# numeric.net
KiCad netlist of a schematic drawn in EAGLE
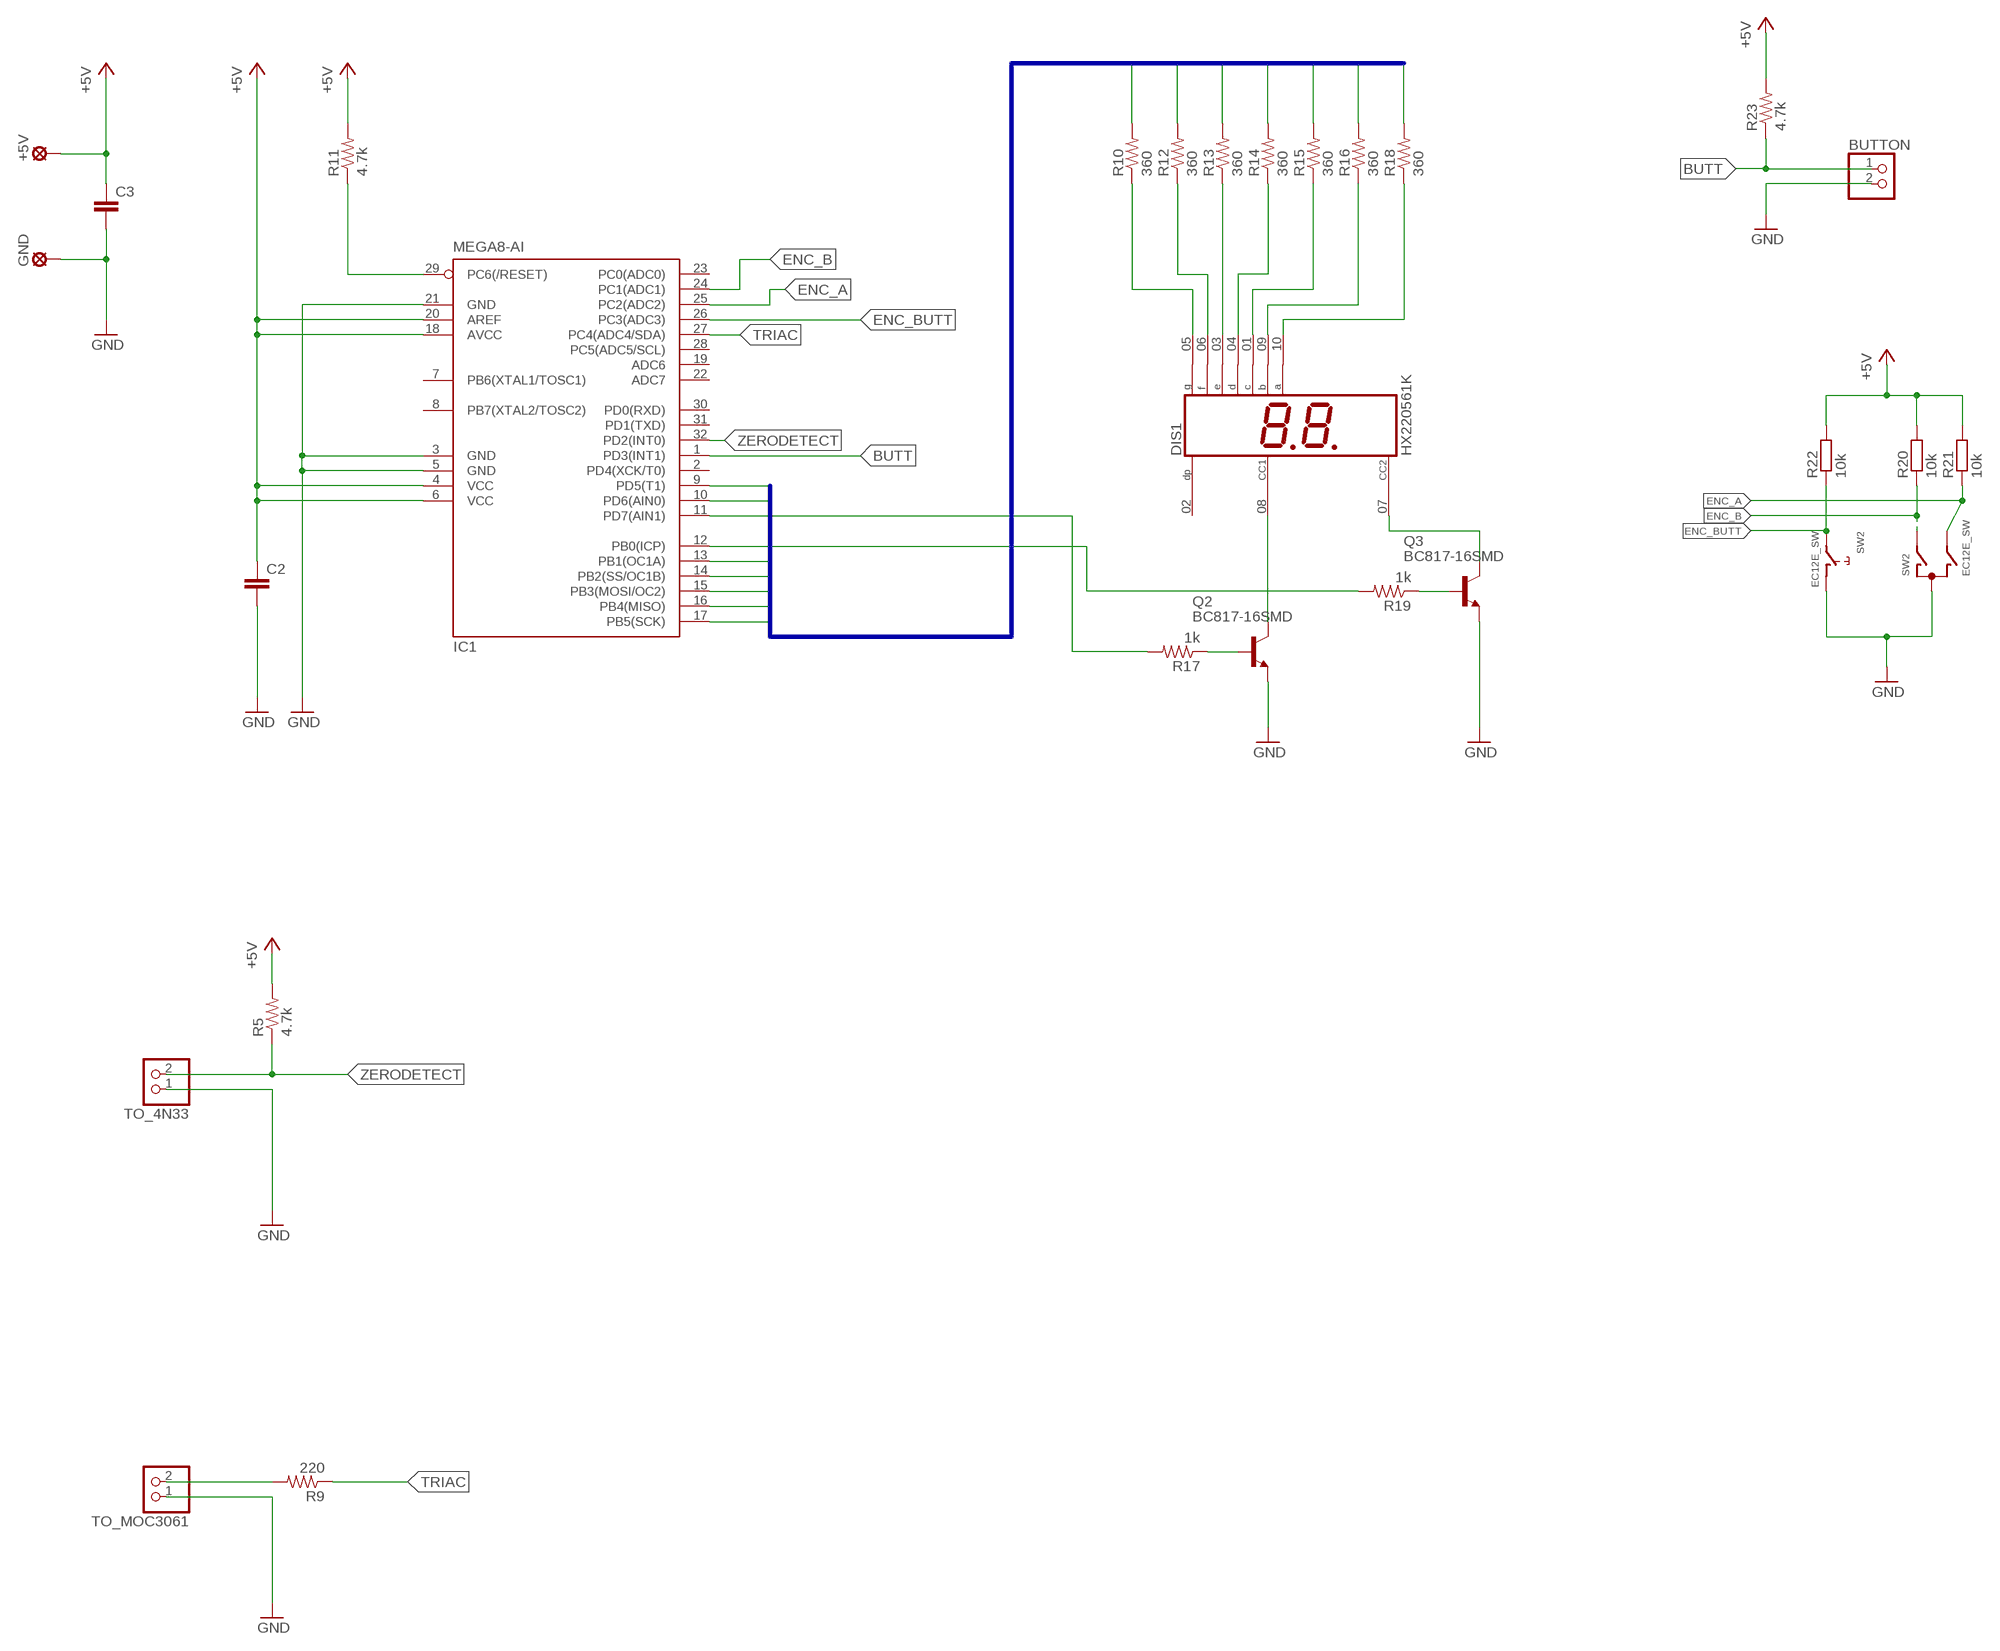
[diagram p0: schematic, sheet 1]

(export (version "E")
  (design (tool "Eeschema 10.0.6"))
  (components
    (comp (ref "+5V")
      (value "LSP10")
      (footprint "eagle-import:LSP10")
      (libsource (lib "eagle-import") (part "LSP10"))
    )
    (comp (ref "BUTTON")
      (value "PINHD-1X2")
      (footprint "eagle-import:1X02")
      (libsource (lib "eagle-import") (part "PINHD-1X2"))
    )
    (comp (ref "C2")
      (value "C-EUC1206K")
      (footprint "eagle-import:C1206K")
      (libsource (lib "eagle-import") (part "C-EUC1206K"))
    )
    (comp (ref "C3")
      (value "C-EUC1206K")
      (footprint "eagle-import:C1206K")
      (libsource (lib "eagle-import") (part "C-EUC1206K"))
    )
    (comp (ref "DIS1")
      (value "HX220561K")
      (footprint "eagle-import:HX220561K")
      (libsource (lib "eagle-import") (part "HX220561K"))
    )
    (comp (ref "GND")
      (value "LSP10")
      (footprint "eagle-import:LSP10")
      (libsource (lib "eagle-import") (part "LSP10"))
    )
    (comp (ref "IC1")
      (value "MEGA8-AI")
      (footprint "eagle-import:TQFP32-08")
      (fields (field (name "MPN") "ATMEGA8-16AU"))
      (libsource (lib "eagle-import") (part "MEGA8-AI"))
    )
    (comp (ref "Q2")
      (value "BC817-16SMD")
      (footprint "eagle-import:SOT23-BEC")
      (libsource (lib "eagle-import") (part "BC817SMD-16"))
    )
    (comp (ref "Q3")
      (value "BC817-16SMD")
      (footprint "eagle-import:SOT23-BEC")
      (libsource (lib "eagle-import") (part "BC817SMD-16"))
    )
    (comp (ref "R5")
      (value "4.7k")
      (footprint "eagle-import:M1206")
      (libsource (lib "eagle-import") (part "R-US_M1206"))
    )
    (comp (ref "R9")
      (value "220")
      (footprint "eagle-import:M1206")
      (libsource (lib "eagle-import") (part "R-US_M1206"))
    )
    (comp (ref "R10")
      (value "360")
      (footprint "eagle-import:M1206")
      (libsource (lib "eagle-import") (part "R-US_M1206"))
    )
    (comp (ref "R11")
      (value "4.7k")
      (footprint "eagle-import:M1206")
      (libsource (lib "eagle-import") (part "R-US_M1206"))
    )
    (comp (ref "R12")
      (value "360")
      (footprint "eagle-import:M1206")
      (libsource (lib "eagle-import") (part "R-US_M1206"))
    )
    (comp (ref "R13")
      (value "360")
      (footprint "eagle-import:M1206")
      (libsource (lib "eagle-import") (part "R-US_M1206"))
    )
    (comp (ref "R14")
      (value "360")
      (footprint "eagle-import:M1206")
      (libsource (lib "eagle-import") (part "R-US_M1206"))
    )
    (comp (ref "R15")
      (value "360")
      (footprint "eagle-import:M1206")
      (libsource (lib "eagle-import") (part "R-US_M1206"))
    )
    (comp (ref "R16")
      (value "360")
      (footprint "eagle-import:M1206")
      (libsource (lib "eagle-import") (part "R-US_M1206"))
    )
    (comp (ref "R17")
      (value "1k")
      (footprint "eagle-import:M1206")
      (libsource (lib "eagle-import") (part "R-US_M1206"))
    )
    (comp (ref "R18")
      (value "360")
      (footprint "eagle-import:M1206")
      (libsource (lib "eagle-import") (part "R-US_M1206"))
    )
    (comp (ref "R19")
      (value "1k")
      (footprint "eagle-import:M1206")
      (libsource (lib "eagle-import") (part "R-US_M1206"))
    )
    (comp (ref "R20")
      (value "10k")
      (footprint "eagle-import:R1206")
      (libsource (lib "eagle-import") (part "R-EU_R1206"))
    )
    (comp (ref "R21")
      (value "10k")
      (footprint "eagle-import:R1206")
      (libsource (lib "eagle-import") (part "R-EU_R1206"))
    )
    (comp (ref "R22")
      (value "10k")
      (footprint "eagle-import:R1206")
      (libsource (lib "eagle-import") (part "R-EU_R1206"))
    )
    (comp (ref "R23")
      (value "4.7k")
      (footprint "eagle-import:M1206")
      (libsource (lib "eagle-import") (part "R-US_M1206"))
    )
    (comp (ref "SW2")
      (value "EC12E_SW")
      (footprint "eagle-import:ALPS_EC12E_SW")
      (fields (field (name "MPN") "EC12E2424407"))
      (libsource (lib "eagle-import") (part "EC12E_SW"))
    )
    (comp (ref "TO_4N33")
      (value "PINHD-1X2")
      (footprint "eagle-import:1X02")
      (libsource (lib "eagle-import") (part "PINHD-1X2"))
    )
    (comp (ref "TO_MOC3061")
      (value "PINHD-1X2")
      (footprint "eagle-import:1X02")
      (libsource (lib "eagle-import") (part "PINHD-1X2"))
    )
  )
  (nets
    (net (code "1") (name "+5V") (class "Default")
      (node (ref "+5V") (pin "MP") (pinfunction "MP_MP") (pintype "passive"))
      (node (ref "C2") (pin "1") (pinfunction "1_1") (pintype "passive"))
      (node (ref "C3") (pin "1") (pinfunction "1_1") (pintype "passive"))
      (node (ref "IC1") (pin "18") (pinfunction "AVCC_18") (pintype "power_in"))
      (node (ref "IC1") (pin "20") (pinfunction "AREF_20") (pintype "passive"))
      (node (ref "IC1") (pin "4") (pinfunction "VCC_4") (pintype "power_in"))
      (node (ref "IC1") (pin "6") (pinfunction "VCC_6") (pintype "power_in"))
      (node (ref "R11") (pin "2") (pinfunction "2_2") (pintype "passive"))
      (node (ref "R20") (pin "2") (pinfunction "2_2") (pintype "passive"))
      (node (ref "R21") (pin "2") (pinfunction "2_2") (pintype "passive"))
      (node (ref "R22") (pin "2") (pinfunction "2_2") (pintype "passive"))
      (node (ref "R23") (pin "2") (pinfunction "2_2") (pintype "passive"))
      (node (ref "R5") (pin "2") (pinfunction "2_2") (pintype "passive"))
    )
    (net (code "2") (name "/B0") (class "Default")
      (node (ref "IC1") (pin "10") (pinfunction "PD6(AIN0)_10") (pintype "bidirectional"))
      (node (ref "R16") (pin "2") (pinfunction "2_2") (pintype "passive"))
    )
    (net (code "3") (name "/B1") (class "Default")
      (node (ref "IC1") (pin "9") (pinfunction "PD5(T1)_9") (pintype "bidirectional"))
      (node (ref "R18") (pin "2") (pinfunction "2_2") (pintype "passive"))
    )
    (net (code "4") (name "/B2") (class "Default")
      (node (ref "IC1") (pin "13") (pinfunction "PB1(OC1A)_13") (pintype "bidirectional"))
      (node (ref "R15") (pin "2") (pinfunction "2_2") (pintype "passive"))
    )
    (net (code "5") (name "/B3") (class "Default")
      (node (ref "IC1") (pin "14") (pinfunction "PB2(SS/OC1B)_14") (pintype "bidirectional"))
      (node (ref "R13") (pin "2") (pinfunction "2_2") (pintype "passive"))
    )
    (net (code "6") (name "/B4") (class "Default")
      (node (ref "IC1") (pin "15") (pinfunction "PB3(MOSI/OC2)_15") (pintype "bidirectional"))
      (node (ref "R14") (pin "2") (pinfunction "2_2") (pintype "passive"))
    )
    (net (code "7") (name "/B5") (class "Default")
      (node (ref "IC1") (pin "16") (pinfunction "PB4(MISO)_16") (pintype "bidirectional"))
      (node (ref "R10") (pin "2") (pinfunction "2_2") (pintype "passive"))
    )
    (net (code "8") (name "/B6") (class "Default")
      (node (ref "IC1") (pin "17") (pinfunction "PB5(SCK)_17") (pintype "bidirectional"))
      (node (ref "R12") (pin "2") (pinfunction "2_2") (pintype "passive"))
    )
    (net (code "9") (name "BUTT") (class "Default")
      (node (ref "BUTTON") (pin "1") (pinfunction "1_1") (pintype "passive"))
      (node (ref "IC1") (pin "1") (pinfunction "PD3(INT1)_1") (pintype "bidirectional"))
      (node (ref "R23") (pin "1") (pinfunction "1_1") (pintype "passive"))
    )
    (net (code "10") (name "ENC_A") (class "Default")
      (node (ref "IC1") (pin "25") (pinfunction "PC2(ADC2)_25") (pintype "bidirectional"))
      (node (ref "R21") (pin "1") (pinfunction "1_1") (pintype "passive"))
      (node (ref "SW2") (pin "B") (pinfunction "B_B") (pintype "passive"))
    )
    (net (code "11") (name "ENC_B") (class "Default")
      (node (ref "IC1") (pin "24") (pinfunction "PC1(ADC1)_24") (pintype "bidirectional"))
      (node (ref "R20") (pin "1") (pinfunction "1_1") (pintype "passive"))
      (node (ref "SW2") (pin "A") (pinfunction "A_A") (pintype "passive"))
    )
    (net (code "12") (name "ENC_BUTT") (class "Default")
      (node (ref "IC1") (pin "26") (pinfunction "PC3(ADC3)_26") (pintype "bidirectional"))
      (node (ref "R22") (pin "1") (pinfunction "1_1") (pintype "passive"))
      (node (ref "SW2") (pin "E") (pinfunction "BUTT_E") (pintype "passive"))
    )
    (net (code "13") (name "GND") (class "Default")
      (node (ref "BUTTON") (pin "2") (pinfunction "2_2") (pintype "passive"))
      (node (ref "C2") (pin "2") (pinfunction "2_2") (pintype "passive"))
      (node (ref "C3") (pin "2") (pinfunction "2_2") (pintype "passive"))
      (node (ref "GND") (pin "MP") (pinfunction "MP_MP") (pintype "passive"))
      (node (ref "IC1") (pin "21") (pinfunction "GND_21") (pintype "power_in"))
      (node (ref "IC1") (pin "3") (pinfunction "GND_3") (pintype "power_in"))
      (node (ref "IC1") (pin "5") (pinfunction "GND_5") (pintype "power_in"))
      (node (ref "Q2") (pin "E") (pinfunction "E_E") (pintype "passive"))
      (node (ref "Q3") (pin "E") (pinfunction "E_E") (pintype "passive"))
      (node (ref "SW2") (pin "C") (pinfunction "C_C") (pintype "passive"))
      (node (ref "SW2") (pin "GND@1") (pinfunction "BUTT_GND_GND@1") (pintype "passive"))
      (node (ref "TO_4N33") (pin "1") (pinfunction "1_1") (pintype "passive"))
      (node (ref "TO_MOC3061") (pin "1") (pinfunction "1_1") (pintype "passive"))
    )
    (net (code "14") (name "Net-(DIS1-A)") (class "Default")
      (node (ref "DIS1") (pin "10") (pinfunction "A_10") (pintype "passive"))
      (node (ref "R18") (pin "1") (pinfunction "1_1") (pintype "passive"))
    )
    (net (code "15") (name "Net-(DIS1-B)") (class "Default")
      (node (ref "DIS1") (pin "09") (pinfunction "B_09") (pintype "passive"))
      (node (ref "R16") (pin "1") (pinfunction "1_1") (pintype "passive"))
    )
    (net (code "16") (name "Net-(DIS1-C)") (class "Default")
      (node (ref "DIS1") (pin "01") (pinfunction "C_01") (pintype "passive"))
      (node (ref "R15") (pin "1") (pinfunction "1_1") (pintype "passive"))
    )
    (net (code "17") (name "Net-(DIS1-CC1)") (class "Default")
      (node (ref "DIS1") (pin "08") (pinfunction "CC1_08") (pintype "passive"))
      (node (ref "Q2") (pin "C") (pinfunction "C_C") (pintype "passive"))
    )
    (net (code "18") (name "Net-(DIS1-CC2)") (class "Default")
      (node (ref "DIS1") (pin "07") (pinfunction "CC2_07") (pintype "passive"))
      (node (ref "Q3") (pin "C") (pinfunction "C_C") (pintype "passive"))
    )
    (net (code "19") (name "Net-(DIS1-D)") (class "Default")
      (node (ref "DIS1") (pin "04") (pinfunction "D_04") (pintype "passive"))
      (node (ref "R14") (pin "1") (pinfunction "1_1") (pintype "passive"))
    )
    (net (code "20") (name "Net-(DIS1-E)") (class "Default")
      (node (ref "DIS1") (pin "03") (pinfunction "E_03") (pintype "passive"))
      (node (ref "R13") (pin "1") (pinfunction "1_1") (pintype "passive"))
    )
    (net (code "21") (name "Net-(DIS1-F)") (class "Default")
      (node (ref "DIS1") (pin "06") (pinfunction "F_06") (pintype "passive"))
      (node (ref "R12") (pin "1") (pinfunction "1_1") (pintype "passive"))
    )
    (net (code "22") (name "Net-(DIS1-G)") (class "Default")
      (node (ref "DIS1") (pin "05") (pinfunction "G_05") (pintype "passive"))
      (node (ref "R10") (pin "1") (pinfunction "1_1") (pintype "passive"))
    )
    (net (code "23") (name "Net-(IC1-PB0(ICP))") (class "Default")
      (node (ref "IC1") (pin "12") (pinfunction "PB0(ICP)_12") (pintype "bidirectional"))
      (node (ref "R19") (pin "2") (pinfunction "2_2") (pintype "passive"))
    )
    (net (code "24") (name "Net-(IC1-PC6({slash}RESET))") (class "Default")
      (node (ref "IC1") (pin "29") (pinfunction "PC6(/RESET)_29") (pintype "bidirectional"))
      (node (ref "R11") (pin "1") (pinfunction "1_1") (pintype "passive"))
    )
    (net (code "25") (name "Net-(IC1-PD7(AIN1))") (class "Default")
      (node (ref "IC1") (pin "11") (pinfunction "PD7(AIN1)_11") (pintype "bidirectional"))
      (node (ref "R17") (pin "2") (pinfunction "2_2") (pintype "passive"))
    )
    (net (code "26") (name "Net-(Q2-PadB)") (class "Default")
      (node (ref "Q2") (pin "B") (pinfunction "B_B") (pintype "passive"))
      (node (ref "R17") (pin "1") (pinfunction "1_1") (pintype "passive"))
    )
    (net (code "27") (name "Net-(Q3-PadB)") (class "Default")
      (node (ref "Q3") (pin "B") (pinfunction "B_B") (pintype "passive"))
      (node (ref "R19") (pin "1") (pinfunction "1_1") (pintype "passive"))
    )
    (net (code "28") (name "Net-(R9-Pad2)") (class "Default")
      (node (ref "R9") (pin "2") (pinfunction "2_2") (pintype "passive"))
      (node (ref "TO_MOC3061") (pin "2") (pinfunction "2_2") (pintype "passive"))
    )
    (net (code "29") (name "TRIAC") (class "Default")
      (node (ref "IC1") (pin "27") (pinfunction "PC4(ADC4/SDA)_27") (pintype "bidirectional"))
      (node (ref "R9") (pin "1") (pinfunction "1_1") (pintype "passive"))
    )
    (net (code "30") (name "ZERODETECT") (class "Default")
      (node (ref "IC1") (pin "32") (pinfunction "PD2(INT0)_32") (pintype "bidirectional"))
      (node (ref "R5") (pin "1") (pinfunction "1_1") (pintype "passive"))
      (node (ref "TO_4N33") (pin "2") (pinfunction "2_2") (pintype "passive"))
    )
    (net (code "31") (name "unconnected-(DIS1-DP-Pad02)") (class "Default")
      (node (ref "DIS1") (pin "02") (pinfunction "DP_02") (pintype "passive"))
    )
    (net (code "32") (name "unconnected-(IC1-ADC6-Pad19)") (class "Default")
      (node (ref "IC1") (pin "19") (pinfunction "ADC6_19") (pintype "bidirectional"))
    )
    (net (code "33") (name "unconnected-(IC1-ADC7-Pad22)") (class "Default")
      (node (ref "IC1") (pin "22") (pinfunction "ADC7_22") (pintype "bidirectional"))
    )
    (net (code "34") (name "unconnected-(IC1-PB6(XTAL1{slash}TOSC1)-Pad7)") (class "Default")
      (node (ref "IC1") (pin "7") (pinfunction "PB6(XTAL1/TOSC1)_7") (pintype "bidirectional"))
    )
    (net (code "35") (name "unconnected-(IC1-PB7(XTAL2{slash}TOSC2)-Pad8)") (class "Default")
      (node (ref "IC1") (pin "8") (pinfunction "PB7(XTAL2/TOSC2)_8") (pintype "bidirectional"))
    )
    (net (code "36") (name "unconnected-(IC1-PC0(ADC0)-Pad23)") (class "Default")
      (node (ref "IC1") (pin "23") (pinfunction "PC0(ADC0)_23") (pintype "bidirectional"))
    )
    (net (code "37") (name "unconnected-(IC1-PC5(ADC5{slash}SCL)-Pad28)") (class "Default")
      (node (ref "IC1") (pin "28") (pinfunction "PC5(ADC5/SCL)_28") (pintype "bidirectional"))
    )
    (net (code "38") (name "unconnected-(IC1-PD0(RXD)-Pad30)") (class "Default")
      (node (ref "IC1") (pin "30") (pinfunction "PD0(RXD)_30") (pintype "bidirectional"))
    )
    (net (code "39") (name "unconnected-(IC1-PD1(TXD)-Pad31)") (class "Default")
      (node (ref "IC1") (pin "31") (pinfunction "PD1(TXD)_31") (pintype "bidirectional"))
    )
    (net (code "40") (name "unconnected-(IC1-PD4(XCK{slash}T0)-Pad2)") (class "Default")
      (node (ref "IC1") (pin "2") (pinfunction "PD4(XCK/T0)_2") (pintype "bidirectional"))
    )
  )
)
